# deskaBezESP.net
KiCad netlist of a schematic drawn in EAGLE
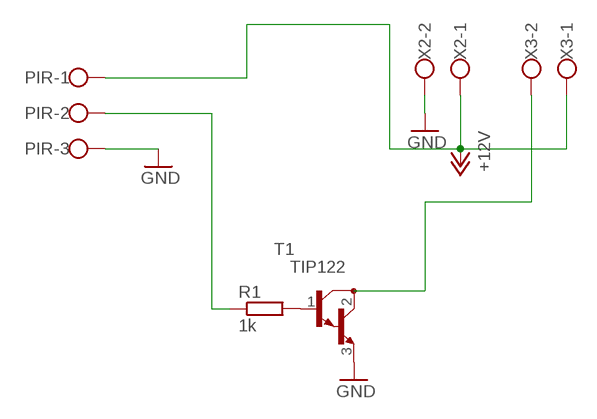
[diagram p0: schematic, sheet 1]

(export (version "E")
  (design (tool "Eeschema 10.0.6"))
  (components
    (comp (ref "PIR")
      (value "W237-103")
      (footprint "eagle-import:W237-103")
      (fields (field (name "MPN") "237-103"))
      (libsource (lib "eagle-import") (part "W237-103"))
    )
    (comp (ref "R1")
      (value "1k")
      (footprint "eagle-import:0207_10")
      (libsource (lib "eagle-import") (part "R-EU_0207/10"))
    )
    (comp (ref "T1")
      (value "TIP122")
      (footprint "eagle-import:TO220")
      (libsource (lib "eagle-import") (part "TIP122"))
    )
    (comp (ref "X2")
      (value "W237-102")
      (footprint "eagle-import:W237-102")
      (fields (field (name "MPN") "237-102"))
      (libsource (lib "eagle-import") (part "W237-102"))
    )
    (comp (ref "X3")
      (value "W237-102")
      (footprint "eagle-import:W237-102")
      (fields (field (name "MPN") "237-102"))
      (libsource (lib "eagle-import") (part "W237-102"))
    )
  )
  (nets
    (net (code "1") (name "+12V") (class "Default")
      (node (ref "PIR") (pin "1") (pinfunction "KL_1") (pintype "passive"))
      (node (ref "X2") (pin "1") (pinfunction "KL_1") (pintype "passive"))
      (node (ref "X3") (pin "1") (pinfunction "KL_1") (pintype "passive"))
    )
    (net (code "2") (name "GND") (class "Default")
      (node (ref "PIR") (pin "3") (pinfunction "KL_3") (pintype "passive"))
      (node (ref "T1") (pin "3") (pinfunction "E_3") (pintype "passive"))
      (node (ref "X2") (pin "2") (pinfunction "KL_2") (pintype "passive"))
    )
    (net (code "3") (name "Net-(PIRB-KL)") (class "Default")
      (node (ref "PIR") (pin "2") (pinfunction "KL_2") (pintype "passive"))
      (node (ref "R1") (pin "1") (pinfunction "1_1") (pintype "passive"))
    )
    (net (code "4") (name "Net-(T1-B)") (class "Default")
      (node (ref "R1") (pin "2") (pinfunction "2_2") (pintype "passive"))
      (node (ref "T1") (pin "1") (pinfunction "B_1") (pintype "passive"))
    )
    (net (code "5") (name "Net-(T1-C)") (class "Default")
      (node (ref "T1") (pin "2") (pinfunction "C_2") (pintype "passive"))
      (node (ref "X3") (pin "2") (pinfunction "KL_2") (pintype "passive"))
    )
  )
)
